# SCH_hackerCard_2023-10-17.net
KiCad netlist of a schematic drawn in EasyEDA
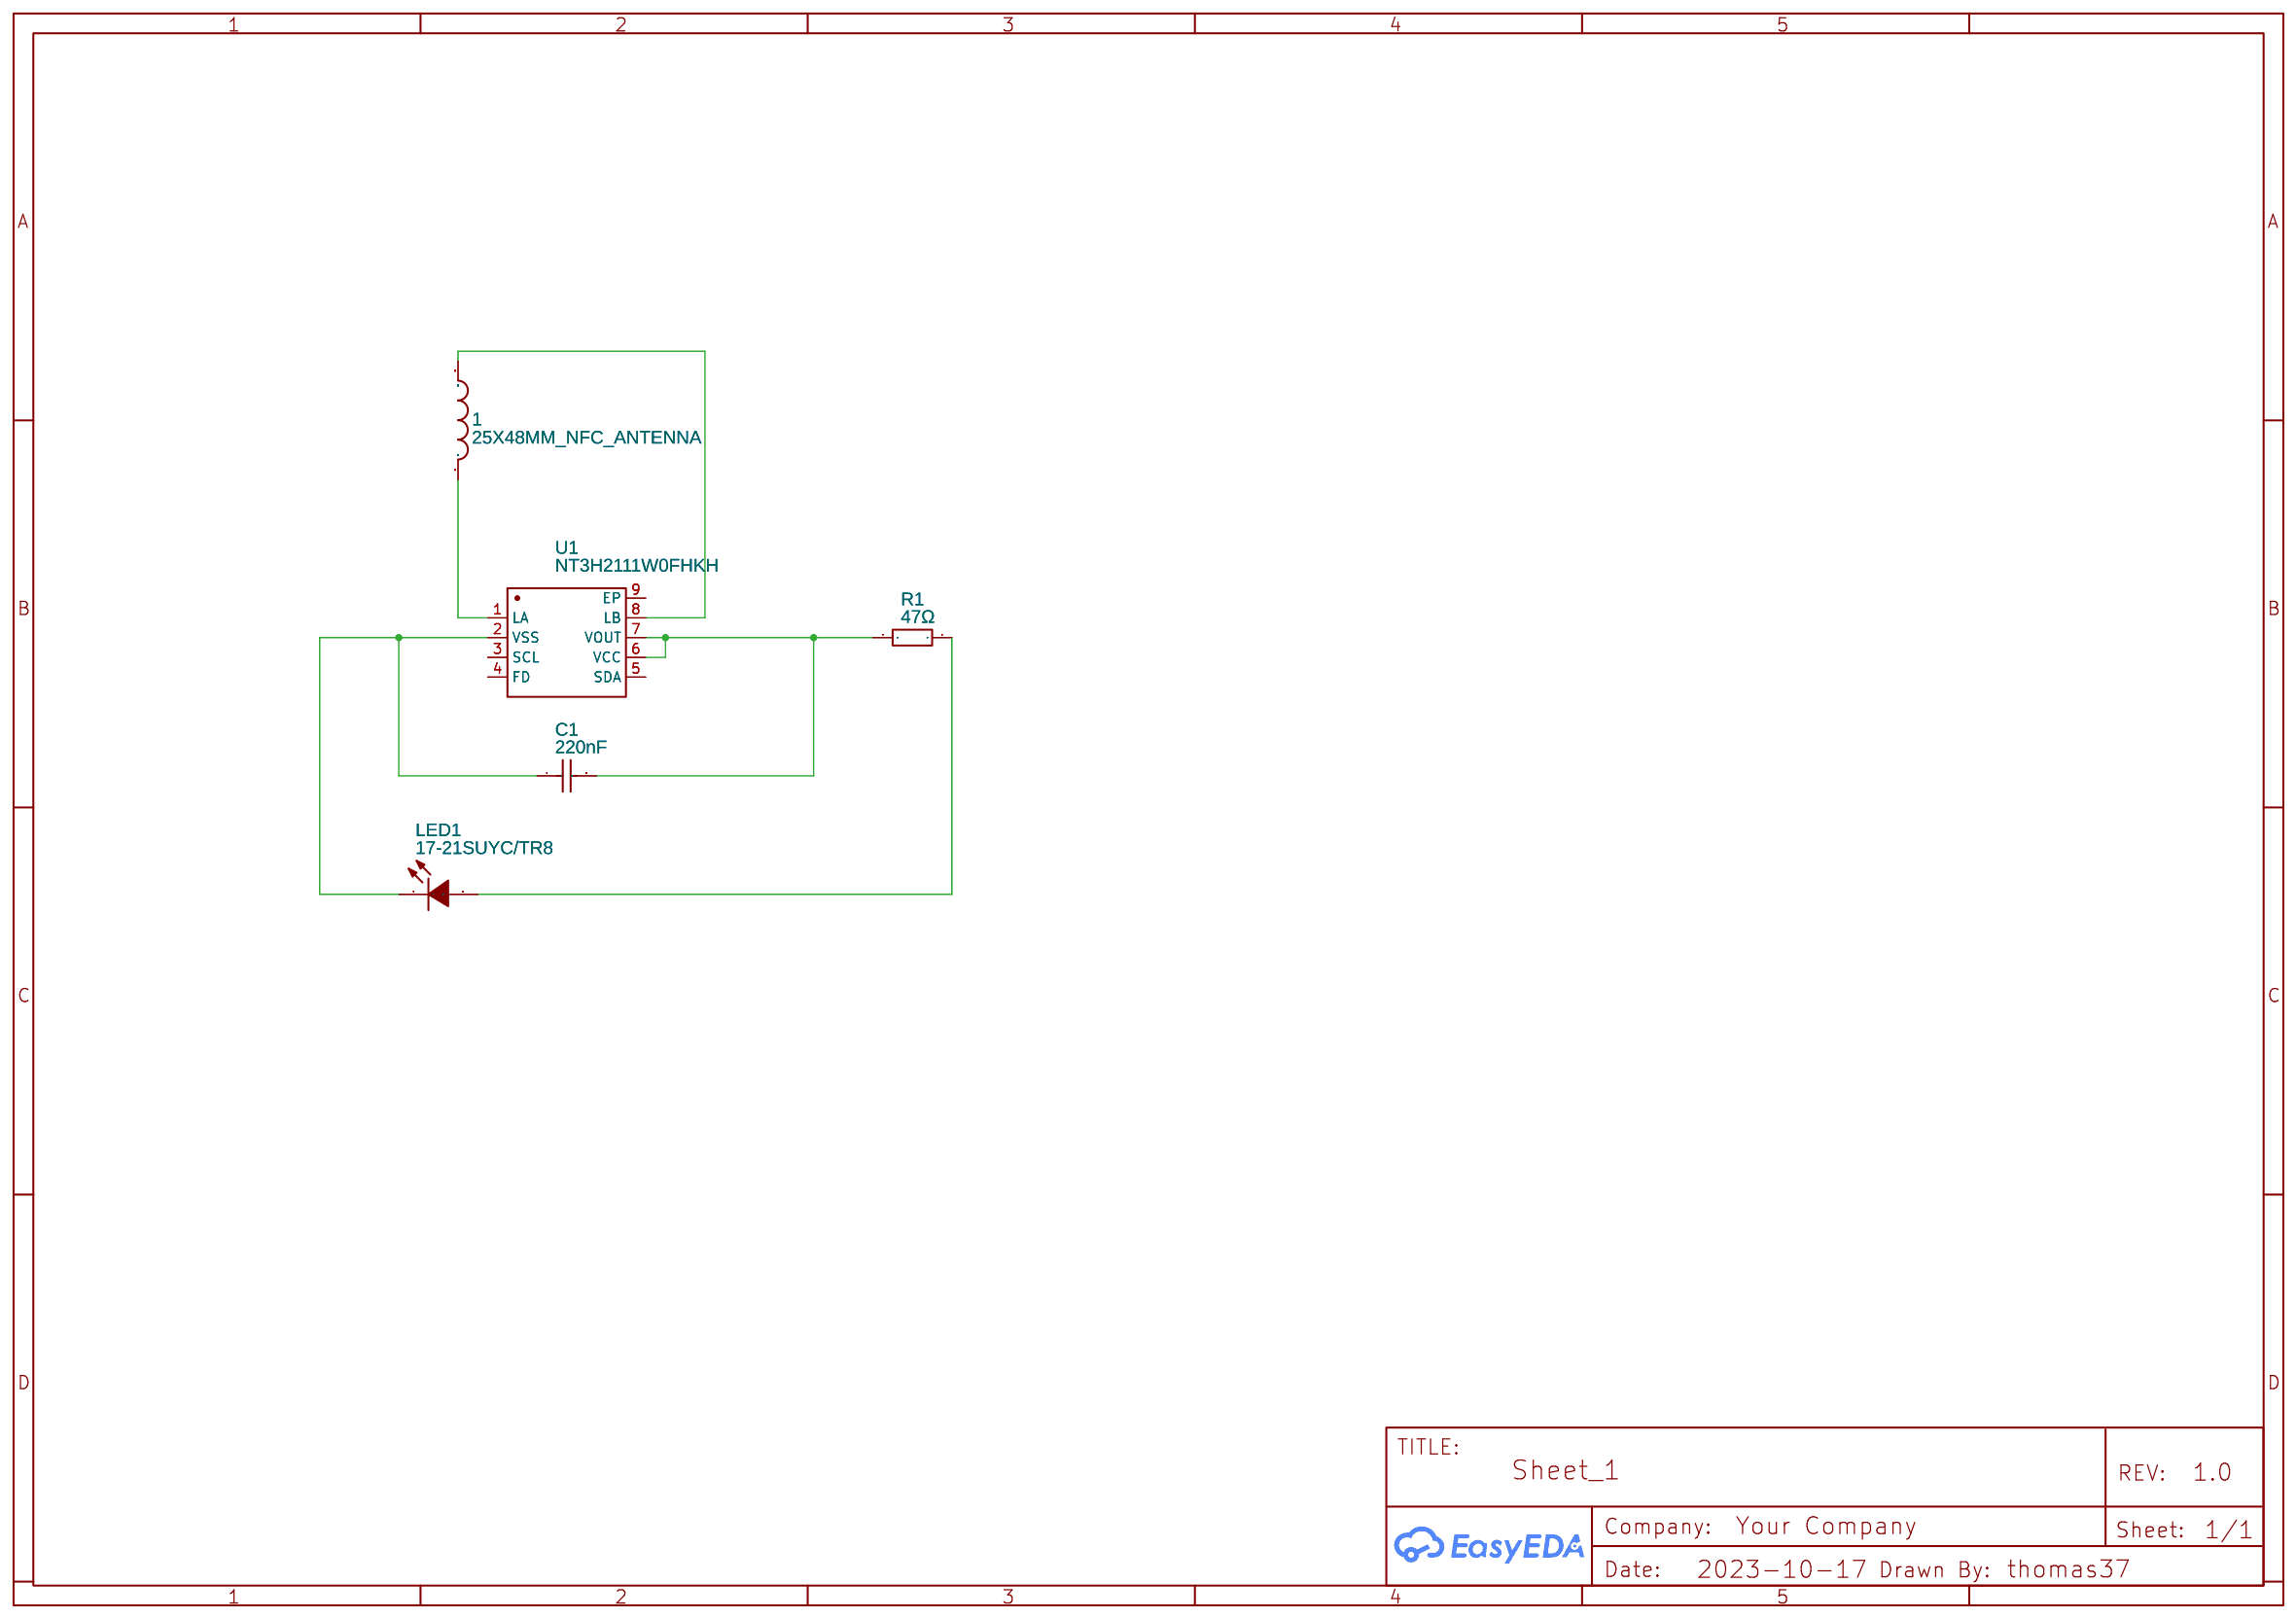
[diagram p0: schematic sheet]

(export (version "E")
  (design (tool "Eeschema 10.0.6"))
  (components
    (comp (ref "1") (value "25X48MM_NFC_ANTENNA") (libsource (lib "") (part "25X48MM_NFC_ANTENNA")))
    (comp (ref "C1")
      (value "220nF")
      (fields
        (field (name "Manufacturer Part") "CL10B224KA8NNNC")
        (field (name "Manufacturer") "SAMSUNG(三星)")
      )
      (libsource (lib "") (part "CL10B224KA8NNNC"))
    )
    (comp (ref "LED1")
      (value "17-21SUYC/TR8")
      (fields (field (name "Manufacturer") "KENTO"))
      (libsource (lib "") (part "17-21SUYC/TR8"))
    )
    (comp (ref "R1")
      (value "47Ω")
      (fields
        (field (name "Manufacturer Part") "0603WAF470JT5E")
        (field (name "Manufacturer") "UNI-ROYAL(厚声)")
      )
      (libsource (lib "") (part "0603WAF470JT5E"))
    )
    (comp (ref "U1")
      (value "NT3H2111W0FHKH")
      (fields (field (name "Manufacturer") "NXP(恩智浦)"))
      (libsource (lib "") (part "NT3H2111W0FHKH"))
    )
  )
  (nets
    (net (code "1") (name "Net-(LED1-+)") (class "Default")
      (node (ref "LED1") (pin "2") (pinfunction "+_2") (pintype "unspecified"))
      (node (ref "R1") (pin "2") (pinfunction "2_2") (pintype "input"))
    )
    (net (code "2") (name "Net-(LED1--)") (class "Default")
      (node (ref "C1") (pin "1") (pinfunction "1_1") (pintype "input"))
      (node (ref "LED1") (pin "1") (pinfunction "-_1") (pintype "unspecified"))
      (node (ref "U1") (pin "2") (pinfunction "VSS_2") (pintype "unspecified"))
    )
    (net (code "3") (name "Net-(U1-LA)") (class "Default")
      (node (ref "1") (pin "P$2") (pinfunction "P$2_P$2") (pintype "bidirectional"))
      (node (ref "U1") (pin "1") (pinfunction "LA_1") (pintype "unspecified"))
    )
    (net (code "4") (name "Net-(U1-LB)") (class "Default")
      (node (ref "1") (pin "P$1") (pinfunction "P$1_P$1") (pintype "bidirectional"))
      (node (ref "U1") (pin "8") (pinfunction "LB_8") (pintype "unspecified"))
    )
    (net (code "5") (name "Net-(U1-VCC)") (class "Default")
      (node (ref "C1") (pin "2") (pinfunction "2_2") (pintype "input"))
      (node (ref "R1") (pin "1") (pinfunction "1_1") (pintype "input"))
      (node (ref "U1") (pin "6") (pinfunction "VCC_6") (pintype "unspecified"))
      (node (ref "U1") (pin "7") (pinfunction "VOUT_7") (pintype "unspecified"))
    )
    (net (code "6") (name "unconnected-(U1-EP-Pad9)") (class "Default")
      (node (ref "U1") (pin "9") (pinfunction "EP_9") (pintype "unspecified"))
    )
    (net (code "7") (name "unconnected-(U1-FD-Pad4)") (class "Default")
      (node (ref "U1") (pin "4") (pinfunction "FD_4") (pintype "unspecified"))
    )
    (net (code "8") (name "unconnected-(U1-SCL-Pad3)") (class "Default")
      (node (ref "U1") (pin "3") (pinfunction "SCL_3") (pintype "unspecified"))
    )
    (net (code "9") (name "unconnected-(U1-SDA-Pad5)") (class "Default")
      (node (ref "U1") (pin "5") (pinfunction "SDA_5") (pintype "unspecified"))
    )
  )
)
